# MCU_MKE185F512VLH16.net
KiCad netlist of a schematic drawn in Altium Designer
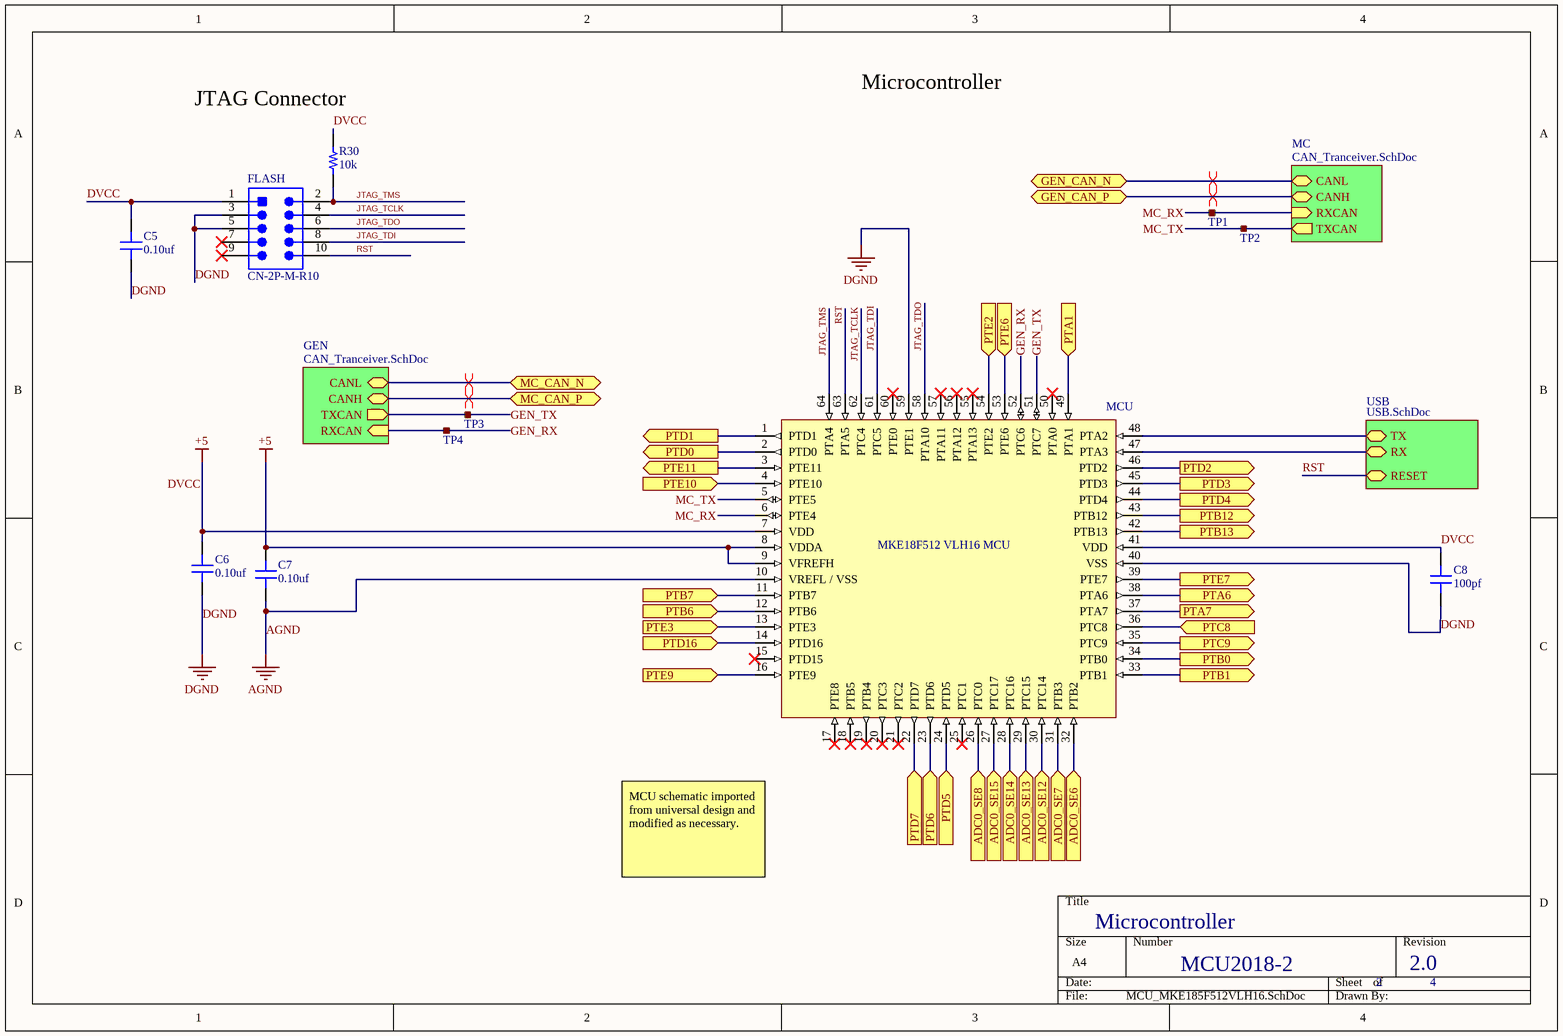
[diagram p0: MCU_MKE185F512VLH16.SchDoc]

(export (version "E")
  (design (tool "Eeschema 10.0.6"))
  (components
    (comp (ref "C5")
      (value "0.10uf")
      (footprint "CAP 0603/1608")
      (fields
        (field (name "Comment") "Capacitor MLCC 0.10uf 16V CAP 0603/1608")
        (field (name "CREATED_BY") "Nick Mah")
      )
      (libsource (lib "Altium-Lib") (part "Capacitor"))
    )
    (comp (ref "C6")
      (value "0.10uf")
      (footprint "CAP 0603/1608")
      (fields
        (field (name "Comment") "Capacitor MLCC 0.10uf 25V CAP 0603/1608")
        (field (name "CREATED_BY") "Nick Mah")
      )
      (libsource (lib "Altium-Lib") (part "Capacitor"))
    )
    (comp (ref "C7")
      (value "0.10uf")
      (footprint "CAP 0603/1608")
      (fields
        (field (name "Comment") "Capacitor MLCC 0.10uf 25V CAP 0603/1608")
        (field (name "CREATED_BY") "Nick Mah")
      )
      (libsource (lib "Altium-Lib") (part "Capacitor"))
    )
    (comp (ref "C8")
      (value "100pf")
      (footprint "CAP 0603/1608")
      (fields
        (field (name "Comment") "Capacitor MLCC 100pf 25V CAP 0603/1608")
        (field (name "CREATED_BY") "Nick Mah")
      )
      (libsource (lib "Altium-Lib") (part "Capacitor"))
    )
    (comp (ref "FLASH")
      (value "CN-2P-M-R10")
      (footprint "HDR2X5_SMT")
      (description "2 row connector")
      (fields (field (name "MFRPARTNO") "5103309-1") (field (name "CREATED_BY") "Aiku"))
      (libsource (lib "Altium-Lib") (part "CN-2P-M-R10"))
    )
    (comp (ref "MCU")
      (value "MKE18F512 VLH16 MCU")
      (footprint "TQFP64")
      (libsource (lib "Altium-Lib") (part "MKE18F512 VLH16 MCU"))
    )
    (comp (ref "R30")
      (value "10k")
      (footprint "RES 0603/1608")
      (fields
        (field (name "TOLERANCE") "1%")
        (field (name "POWER") "1/10W")
        (field (name "Comment") "Resistor 10k 0603 1/10W 1%")
        (field (name "CREATED_BY") "Nick Mah")
      )
      (libsource (lib "Altium-Lib") (part "Resistor"))
    )
    (comp (ref "TP1") (value "RCU-0C") (footprint "RCU-0C") (libsource (lib "Altium-Lib") (part "RCU-0C")))
    (comp (ref "TP2") (value "RCU-0C") (footprint "RCU-0C") (libsource (lib "Altium-Lib") (part "RCU-0C")))
    (comp (ref "TP3") (value "RCU-0C") (footprint "RCU-0C") (libsource (lib "Altium-Lib") (part "RCU-0C")))
    (comp (ref "TP4") (value "RCU-0C") (footprint "RCU-0C") (libsource (lib "Altium-Lib") (part "RCU-0C")))
  )
  (nets
    (net (code "1") (name "+5") (class "Default")
      (node (ref "C5") (pin "2") (pinfunction "2_2") (pintype "passive"))
      (node (ref "C6") (pin "2") (pinfunction "2_2") (pintype "passive"))
      (node (ref "C7") (pin "2") (pinfunction "2_2") (pintype "passive"))
      (node (ref "C8") (pin "2") (pinfunction "2_2") (pintype "passive"))
      (node (ref "FLASH") (pin "1") (pinfunction "1_1") (pintype "passive"))
      (node (ref "MCU") (pin "41") (pinfunction "VDD_41") (pintype "input"))
      (node (ref "MCU") (pin "7") (pinfunction "VDD_7") (pintype "input"))
      (node (ref "MCU") (pin "8") (pinfunction "VDDA_8") (pintype "input"))
      (node (ref "MCU") (pin "9") (pinfunction "VFREFH_9") (pintype "input"))
      (node (ref "R30") (pin "2") (pinfunction "2_2") (pintype "passive"))
    )
    (net (code "2") (name "/ADC0_SE6") (class "Default")
      (node (ref "MCU") (pin "32") (pinfunction "PTB2_32") (pintype "input"))
    )
    (net (code "3") (name "/ADC0_SE7") (class "Default")
      (node (ref "MCU") (pin "31") (pinfunction "PTB3_31") (pintype "input"))
    )
    (net (code "4") (name "/ADC0_SE8") (class "Default")
      (node (ref "MCU") (pin "26") (pinfunction "PTC0_26") (pintype "input"))
    )
    (net (code "5") (name "/ADC0_SE12") (class "Default")
      (node (ref "MCU") (pin "30") (pinfunction "PTC14_30") (pintype "input"))
    )
    (net (code "6") (name "/ADC0_SE13") (class "Default")
      (node (ref "MCU") (pin "29") (pinfunction "PTC15_29") (pintype "input"))
    )
    (net (code "7") (name "/ADC0_SE14") (class "Default")
      (node (ref "MCU") (pin "28") (pinfunction "PTC16_28") (pintype "input"))
    )
    (net (code "8") (name "/ADC0_SE15") (class "Default")
      (node (ref "MCU") (pin "27") (pinfunction "PTC17_27") (pintype "input"))
    )
    (net (code "11") (name "/GEN_RX") (class "Default")
      (node (ref "MCU") (pin "52") (pinfunction "PTC6_52") (pintype "bidirectional"))
      (node (ref "TP4") (pin "1") (pintype "passive"))
    )
    (net (code "12") (name "/GEN_TX") (class "Default")
      (node (ref "MCU") (pin "51") (pinfunction "PTC7_51") (pintype "bidirectional"))
      (node (ref "TP3") (pin "1") (pintype "passive"))
    )
    (net (code "13") (name "/JTAG_TCLK") (class "Default")
      (node (ref "FLASH") (pin "4") (pinfunction "4_4") (pintype "passive"))
      (node (ref "MCU") (pin "62") (pinfunction "PTC4_62") (pintype "input"))
    )
    (net (code "14") (name "/JTAG_TDI") (class "Default")
      (node (ref "FLASH") (pin "8") (pinfunction "8_8") (pintype "passive"))
      (node (ref "MCU") (pin "61") (pinfunction "PTC5_61") (pintype "input"))
    )
    (net (code "15") (name "/JTAG_TDO") (class "Default")
      (node (ref "FLASH") (pin "6") (pinfunction "6_6") (pintype "passive"))
      (node (ref "MCU") (pin "58") (pinfunction "PTA10_58") (pintype "input"))
    )
    (net (code "16") (name "/JTAG_TMS") (class "Default")
      (node (ref "FLASH") (pin "2") (pinfunction "2_2") (pintype "passive"))
      (node (ref "MCU") (pin "64") (pinfunction "PTA4_64") (pintype "input"))
      (node (ref "R30") (pin "1") (pinfunction "1_1") (pintype "passive"))
    )
    (net (code "19") (name "/MC_RX") (class "Default")
      (node (ref "MCU") (pin "6") (pinfunction "PTE4_6") (pintype "bidirectional"))
      (node (ref "TP1") (pin "1") (pintype "passive"))
    )
    (net (code "20") (name "/MC_TX") (class "Default")
      (node (ref "MCU") (pin "5") (pinfunction "PTE5_5") (pintype "bidirectional"))
      (node (ref "TP2") (pin "1") (pintype "passive"))
    )
    (net (code "21") (name "/PTA1") (class "Default")
      (node (ref "MCU") (pin "49") (pinfunction "PTA1_49") (pintype "input"))
    )
    (net (code "22") (name "/PTA6") (class "Default")
      (node (ref "MCU") (pin "38") (pinfunction "PTA6_38") (pintype "output"))
    )
    (net (code "23") (name "/PTA7") (class "Default")
      (node (ref "MCU") (pin "37") (pinfunction "PTA7_37") (pintype "output"))
    )
    (net (code "24") (name "/PTB0") (class "Default")
      (node (ref "MCU") (pin "34") (pinfunction "PTB0_34") (pintype "input"))
    )
    (net (code "25") (name "/PTB1") (class "Default")
      (node (ref "MCU") (pin "33") (pinfunction "PTB1_33") (pintype "input"))
    )
    (net (code "26") (name "/PTB6") (class "Default")
      (node (ref "MCU") (pin "12") (pinfunction "PTB6_12") (pintype "input"))
    )
    (net (code "27") (name "/PTB7") (class "Default")
      (node (ref "MCU") (pin "11") (pinfunction "PTB7_11") (pintype "input"))
    )
    (net (code "28") (name "/PTB12") (class "Default")
      (node (ref "MCU") (pin "43") (pinfunction "PTB12_43") (pintype "output"))
    )
    (net (code "29") (name "/PTB13") (class "Default")
      (node (ref "MCU") (pin "42") (pinfunction "PTB13_42") (pintype "output"))
    )
    (net (code "30") (name "/PTC8") (class "Default")
      (node (ref "MCU") (pin "36") (pinfunction "PTC8_36") (pintype "output"))
    )
    (net (code "31") (name "/PTC9") (class "Default")
      (node (ref "MCU") (pin "35") (pinfunction "PTC9_35") (pintype "input"))
    )
    (net (code "32") (name "/PTD0") (class "Default")
      (node (ref "MCU") (pin "2") (pinfunction "PTD0_2") (pintype "output"))
    )
    (net (code "33") (name "/PTD1") (class "Default")
      (node (ref "MCU") (pin "1") (pinfunction "PTD1_1") (pintype "output"))
    )
    (net (code "34") (name "/PTD2") (class "Default")
      (node (ref "MCU") (pin "46") (pinfunction "PTD2_46") (pintype "output"))
    )
    (net (code "35") (name "/PTD3") (class "Default")
      (node (ref "MCU") (pin "45") (pinfunction "PTD3_45") (pintype "output"))
    )
    (net (code "36") (name "/PTD4") (class "Default")
      (node (ref "MCU") (pin "44") (pinfunction "PTD4_44") (pintype "output"))
    )
    (net (code "37") (name "/PTD5") (class "Default")
      (node (ref "MCU") (pin "24") (pinfunction "PTD5_24") (pintype "input"))
    )
    (net (code "38") (name "/PTD6") (class "Default")
      (node (ref "MCU") (pin "23") (pinfunction "PTD6_23") (pintype "output"))
    )
    (net (code "39") (name "/PTD7") (class "Default")
      (node (ref "MCU") (pin "22") (pinfunction "PTD7_22") (pintype "output"))
    )
    (net (code "40") (name "/PTD16") (class "Default")
      (node (ref "MCU") (pin "14") (pinfunction "PTD16_14") (pintype "input"))
    )
    (net (code "41") (name "/PTE2") (class "Default")
      (node (ref "MCU") (pin "54") (pinfunction "PTE2_54") (pintype "input"))
    )
    (net (code "42") (name "/PTE3") (class "Default")
      (node (ref "MCU") (pin "13") (pinfunction "PTE3_13") (pintype "input"))
    )
    (net (code "43") (name "/PTE6") (class "Default")
      (node (ref "MCU") (pin "53") (pinfunction "PTE6_53") (pintype "input"))
    )
    (net (code "44") (name "/PTE7") (class "Default")
      (node (ref "MCU") (pin "39") (pinfunction "PTE7_39") (pintype "output"))
    )
    (net (code "45") (name "/PTE9") (class "Default")
      (node (ref "MCU") (pin "16") (pinfunction "PTE9_16") (pintype "input"))
    )
    (net (code "46") (name "/PTE10") (class "Default")
      (node (ref "MCU") (pin "4") (pinfunction "PTE10_4") (pintype "input"))
    )
    (net (code "47") (name "/PTE11") (class "Default")
      (node (ref "MCU") (pin "3") (pinfunction "PTE11_3") (pintype "input"))
    )
    (net (code "48") (name "/RST") (class "Default")
      (node (ref "FLASH") (pin "10") (pinfunction "10_10") (pintype "passive"))
      (node (ref "MCU") (pin "63") (pinfunction "PTA5_63") (pintype "input"))
    )
    (net (code "49") (name "/RX") (class "Default")
      (node (ref "MCU") (pin "47") (pinfunction "PTA3_47") (pintype "input"))
    )
    (net (code "50") (name "/TX") (class "Default")
      (node (ref "MCU") (pin "48") (pinfunction "PTA2_48") (pintype "input"))
    )
    (net (code "51") (name "AGND") (class "Default")
      (node (ref "C7") (pin "1") (pinfunction "1_1") (pintype "passive"))
      (node (ref "MCU") (pin "10") (pinfunction "VREFL_/_VSS_10") (pintype "input"))
    )
    (net (code "52") (name "DGND") (class "Default")
      (node (ref "C5") (pin "1") (pinfunction "1_1") (pintype "passive"))
      (node (ref "C6") (pin "1") (pinfunction "1_1") (pintype "passive"))
      (node (ref "C8") (pin "1") (pinfunction "1_1") (pintype "passive"))
      (node (ref "FLASH") (pin "3") (pinfunction "3_3") (pintype "passive"))
      (node (ref "FLASH") (pin "5") (pinfunction "5_5") (pintype "passive"))
      (node (ref "MCU") (pin "40") (pinfunction "VSS_40") (pintype "input"))
      (node (ref "MCU") (pin "59") (pinfunction "PTE1_59") (pintype "input"))
    )
    (net (code "53") (name "unconnected-(FLASH-Pad7)") (class "Default")
      (node (ref "FLASH") (pin "7") (pinfunction "7_7") (pintype "passive+no_connect"))
    )
    (net (code "54") (name "unconnected-(FLASH-Pad9)") (class "Default")
      (node (ref "FLASH") (pin "9") (pinfunction "9_9") (pintype "passive+no_connect"))
    )
    (net (code "55") (name "unconnected-(MCU-PTA0-Pad50)") (class "Default")
      (node (ref "MCU") (pin "50") (pinfunction "PTA0_50") (pintype "input+no_connect"))
    )
    (net (code "56") (name "unconnected-(MCU-PTA11-Pad57)") (class "Default")
      (node (ref "MCU") (pin "57") (pinfunction "PTA11_57") (pintype "input+no_connect"))
    )
    (net (code "57") (name "unconnected-(MCU-PTA12-Pad56)") (class "Default")
      (node (ref "MCU") (pin "56") (pinfunction "PTA12_56") (pintype "input+no_connect"))
    )
    (net (code "58") (name "unconnected-(MCU-PTA13-Pad55)") (class "Default")
      (node (ref "MCU") (pin "55") (pinfunction "PTA13_55") (pintype "input+no_connect"))
    )
    (net (code "59") (name "unconnected-(MCU-PTB4-Pad19)") (class "Default")
      (node (ref "MCU") (pin "19") (pinfunction "PTB4_19") (pintype "output+no_connect"))
    )
    (net (code "60") (name "unconnected-(MCU-PTB5-Pad18)") (class "Default")
      (node (ref "MCU") (pin "18") (pinfunction "PTB5_18") (pintype "input+no_connect"))
    )
    (net (code "61") (name "unconnected-(MCU-PTC1-Pad25)") (class "Default")
      (node (ref "MCU") (pin "25") (pinfunction "PTC1_25") (pintype "input+no_connect"))
    )
    (net (code "62") (name "unconnected-(MCU-PTC2-Pad21)") (class "Default")
      (node (ref "MCU") (pin "21") (pinfunction "PTC2_21") (pintype "output+no_connect"))
    )
    (net (code "63") (name "unconnected-(MCU-PTC3-Pad20)") (class "Default")
      (node (ref "MCU") (pin "20") (pinfunction "PTC3_20") (pintype "output+no_connect"))
    )
    (net (code "64") (name "unconnected-(MCU-PTD15-Pad15)") (class "Default")
      (node (ref "MCU") (pin "15") (pinfunction "PTD15_15") (pintype "input+no_connect"))
    )
    (net (code "65") (name "unconnected-(MCU-PTE0-Pad60)") (class "Default")
      (node (ref "MCU") (pin "60") (pinfunction "PTE0_60") (pintype "input+no_connect"))
    )
    (net (code "66") (name "unconnected-(MCU-PTE8-Pad17)") (class "Default")
      (node (ref "MCU") (pin "17") (pinfunction "PTE8_17") (pintype "input+no_connect"))
    )
  )
)
